# KC_Buffer_Schematic.net
KiCad netlist of a schematic drawn in Altium Designer
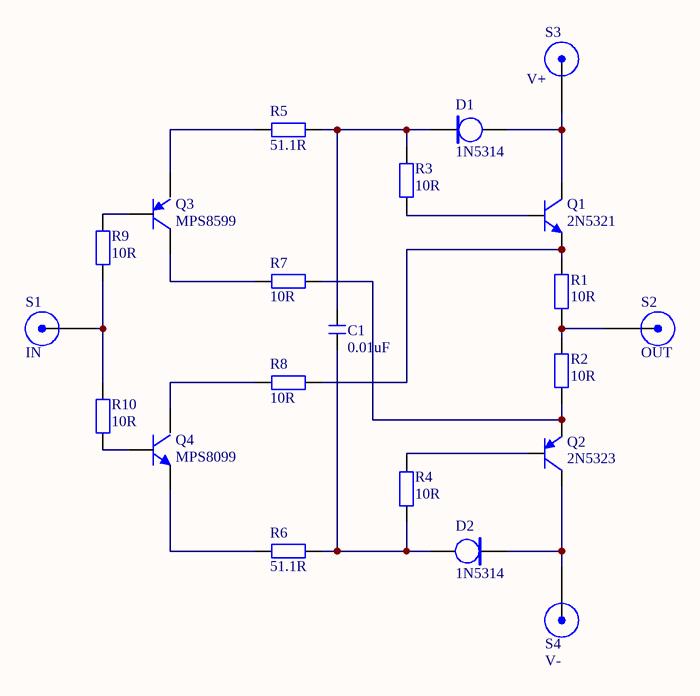
[diagram p0: KC_Buffer_Schematic.SchDoc]

(export (version "E")
  (design (tool "Eeschema 10.0.6"))
  (components
    (comp (ref "C1")
      (value "0.01uF")
      (footprint "CBB 6.3*6.3*5")
      (description "CBB电容")
      (fields (field (name "版权归属") "源创客"))
      (libsource (lib "电阻-电容-电感") (part "C-CBB"))
    )
    (comp (ref "D1")
      (value "1N5314")
      (footprint "DO-41G")
      (description "Current Regulator Diodes")
      (libsource (lib "二极管-整流桥") (part "1N5xxx"))
    )
    (comp (ref "D2")
      (value "1N5314")
      (footprint "DO-41G")
      (description "Current Regulator Diodes")
      (libsource (lib "二极管-整流桥") (part "1N5xxx"))
    )
    (comp (ref "Q1")
      (value "2N5321")
      (footprint "TO39_SMALLHOLE")
      (description "中功率放大-NPN型 100V/1.2a")
      (libsource (lib "三极管") (part "2N5320/5321"))
    )
    (comp (ref "Q2")
      (value "2N5323")
      (footprint "TO39_SMALLHOLE")
      (description "中功率放大-PNP型 100V/1.2a")
      (libsource (lib "三极管") (part "2N5322/5323"))
    )
    (comp (ref "Q3")
      (value "MPS8599")
      (footprint "TO92A_SmallHole")
      (description "音频放大-PNP型")
      (libsource (lib "三极管") (part "MPS8598/8599"))
    )
    (comp (ref "Q4")
      (value "MPS8099")
      (footprint "TO92A_SmallHole")
      (description "音频放大-NPN型")
      (libsource (lib "三极管") (part "MPS8098/8099"))
    )
    (comp (ref "R1")
      (value "10R")
      (footprint "RS 2W")
      (description "直插色环电阻")
      (fields (field (name "版权归属") "源创客"))
      (libsource (lib "电阻-电容-电感") (part "R-CRR"))
    )
    (comp (ref "R2")
      (value "10R")
      (footprint "RS 2W")
      (description "直插色环电阻")
      (fields (field (name "版权归属") "源创客"))
      (libsource (lib "电阻-电容-电感") (part "R-CRR"))
    )
    (comp (ref "R3")
      (value "10R")
      (footprint "RS 1/4W")
      (description "直插色环电阻")
      (fields (field (name "版权归属") "源创客"))
      (libsource (lib "电阻-电容-电感") (part "R-CRR"))
    )
    (comp (ref "R4")
      (value "10R")
      (footprint "RS 1/4W")
      (description "直插色环电阻")
      (fields (field (name "版权归属") "源创客"))
      (libsource (lib "电阻-电容-电感") (part "R-CRR"))
    )
    (comp (ref "R5")
      (value "51.1R")
      (footprint "RS 1/4W")
      (description "直插色环电阻")
      (fields (field (name "版权归属") "源创客"))
      (libsource (lib "电阻-电容-电感") (part "R-CRR"))
    )
    (comp (ref "R6")
      (value "51.1R")
      (footprint "RS 1/4W")
      (description "直插色环电阻")
      (fields (field (name "版权归属") "源创客"))
      (libsource (lib "电阻-电容-电感") (part "R-CRR"))
    )
    (comp (ref "R7")
      (value "10R")
      (footprint "RS 1/4W")
      (description "直插色环电阻")
      (fields (field (name "版权归属") "源创客"))
      (libsource (lib "电阻-电容-电感") (part "R-CRR"))
    )
    (comp (ref "R8")
      (value "10R")
      (footprint "RS 1/4W")
      (description "直插色环电阻")
      (fields (field (name "版权归属") "源创客"))
      (libsource (lib "电阻-电容-电感") (part "R-CRR"))
    )
    (comp (ref "R9")
      (value "10R")
      (footprint "RS 1/4W")
      (description "直插色环电阻")
      (fields (field (name "版权归属") "源创客"))
      (libsource (lib "电阻-电容-电感") (part "R-CRR"))
    )
    (comp (ref "R10")
      (value "10R")
      (footprint "RS 1/4W")
      (description "直插色环电阻")
      (fields (field (name "版权归属") "源创客"))
      (libsource (lib "电阻-电容-电感") (part "R-CRR"))
    )
    (comp (ref "S1")
      (value "IN")
      (footprint "Screw-M4-Small")
      (description "Screw Connector")
      (libsource (lib "Connectors") (part "ScrewConnector"))
    )
    (comp (ref "S2")
      (value "OUT")
      (footprint "Screw-M4-Small")
      (description "Screw Connector")
      (libsource (lib "Connectors") (part "ScrewConnector"))
    )
    (comp (ref "S3")
      (value "V+")
      (footprint "Screw-M4-Small")
      (description "Screw Connector")
      (libsource (lib "Connectors") (part "ScrewConnector"))
    )
    (comp (ref "S4")
      (value "V-")
      (footprint "Screw-M4-Small")
      (description "Screw Connector")
      (libsource (lib "Connectors") (part "ScrewConnector"))
    )
  )
  (nets
    (net (code "1") (name "Net-(D1-Anode)") (class "Default")
      (node (ref "D1") (pin "2") (pinfunction "Anode_2") (pintype "passive"))
      (node (ref "Q1") (pin "2") (pinfunction "C_2") (pintype "passive"))
      (node (ref "S3") (pin "1") (pinfunction "X_1") (pintype "passive"))
    )
    (net (code "2") (name "Net-(D1-Cathode)") (class "Default")
      (node (ref "C1") (pin "2") (pinfunction "2_2") (pintype "passive"))
      (node (ref "D1") (pin "1") (pinfunction "Cathode_1") (pintype "passive"))
      (node (ref "R3") (pin "2") (pinfunction "2_2") (pintype "passive"))
      (node (ref "R5") (pin "1") (pinfunction "1_1") (pintype "passive"))
    )
    (net (code "3") (name "Net-(D2-Anode)") (class "Default")
      (node (ref "C1") (pin "1") (pinfunction "1_1") (pintype "passive"))
      (node (ref "D2") (pin "2") (pinfunction "Anode_2") (pintype "passive"))
      (node (ref "R4") (pin "1") (pinfunction "1_1") (pintype "passive"))
      (node (ref "R6") (pin "1") (pinfunction "1_1") (pintype "passive"))
    )
    (net (code "4") (name "Net-(D2-Cathode)") (class "Default")
      (node (ref "D2") (pin "1") (pinfunction "Cathode_1") (pintype "passive"))
      (node (ref "Q2") (pin "2") (pinfunction "C_2") (pintype "passive"))
      (node (ref "S4") (pin "1") (pinfunction "X_1") (pintype "passive"))
    )
    (net (code "5") (name "Net-(Q1-B)") (class "Default")
      (node (ref "Q1") (pin "3") (pinfunction "B_3") (pintype "passive"))
      (node (ref "R3") (pin "1") (pinfunction "1_1") (pintype "passive"))
    )
    (net (code "6") (name "Net-(Q1-E)") (class "Default")
      (node (ref "Q1") (pin "1") (pinfunction "E_1") (pintype "passive"))
      (node (ref "R1") (pin "2") (pinfunction "2_2") (pintype "passive"))
      (node (ref "R8") (pin "2") (pinfunction "2_2") (pintype "passive"))
    )
    (net (code "7") (name "Net-(Q2-B)") (class "Default")
      (node (ref "Q2") (pin "3") (pinfunction "B_3") (pintype "passive"))
      (node (ref "R4") (pin "2") (pinfunction "2_2") (pintype "passive"))
    )
    (net (code "8") (name "Net-(Q2-E)") (class "Default")
      (node (ref "Q2") (pin "1") (pinfunction "E_1") (pintype "passive"))
      (node (ref "R2") (pin "1") (pinfunction "1_1") (pintype "passive"))
      (node (ref "R7") (pin "2") (pinfunction "2_2") (pintype "passive"))
    )
    (net (code "9") (name "Net-(Q3-B)") (class "Default")
      (node (ref "Q3") (pin "1") (pinfunction "B_1") (pintype "passive"))
      (node (ref "R9") (pin "2") (pinfunction "2_2") (pintype "passive"))
    )
    (net (code "10") (name "Net-(Q3-C)") (class "Default")
      (node (ref "Q3") (pin "2") (pinfunction "C_2") (pintype "passive"))
      (node (ref "R7") (pin "1") (pinfunction "1_1") (pintype "passive"))
    )
    (net (code "11") (name "Net-(Q3-E)") (class "Default")
      (node (ref "Q3") (pin "3") (pinfunction "E_3") (pintype "passive"))
      (node (ref "R5") (pin "2") (pinfunction "2_2") (pintype "passive"))
    )
    (net (code "12") (name "Net-(Q4-B)") (class "Default")
      (node (ref "Q4") (pin "1") (pinfunction "B_1") (pintype "passive"))
      (node (ref "R10") (pin "1") (pinfunction "1_1") (pintype "passive"))
    )
    (net (code "13") (name "Net-(Q4-C)") (class "Default")
      (node (ref "Q4") (pin "2") (pinfunction "C_2") (pintype "passive"))
      (node (ref "R8") (pin "1") (pinfunction "1_1") (pintype "passive"))
    )
    (net (code "14") (name "Net-(Q4-E)") (class "Default")
      (node (ref "Q4") (pin "3") (pinfunction "E_3") (pintype "passive"))
      (node (ref "R6") (pin "2") (pinfunction "2_2") (pintype "passive"))
    )
    (net (code "15") (name "Net-(S1-X)") (class "Default")
      (node (ref "R10") (pin "2") (pinfunction "2_2") (pintype "passive"))
      (node (ref "R9") (pin "1") (pinfunction "1_1") (pintype "passive"))
      (node (ref "S1") (pin "1") (pinfunction "X_1") (pintype "passive"))
    )
    (net (code "16") (name "Net-(S2-X)") (class "Default")
      (node (ref "R1") (pin "1") (pinfunction "1_1") (pintype "passive"))
      (node (ref "R2") (pin "2") (pinfunction "2_2") (pintype "passive"))
      (node (ref "S2") (pin "1") (pinfunction "X_1") (pintype "passive"))
    )
  )
)
